# CPU.net
KiCad netlist of a schematic drawn in Altium Designer
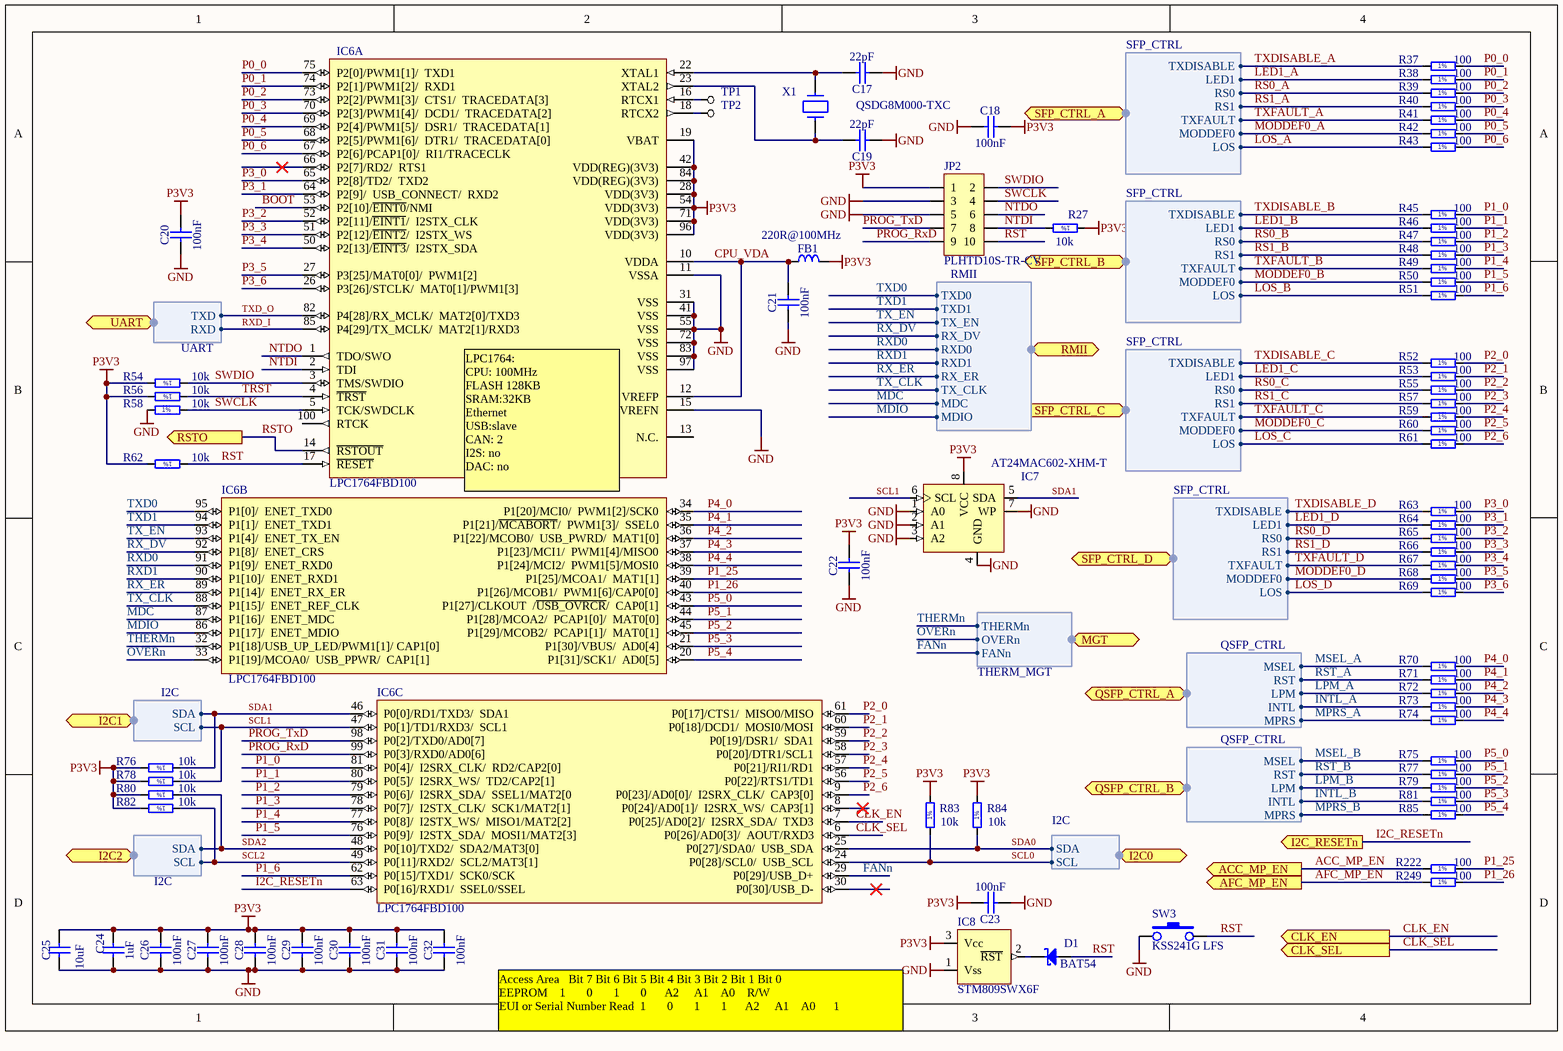
[diagram p0: CPU.SchDoc]

(export (version "E")
  (design (tool "Eeschema 10.0.6"))
  (components
    (comp (ref "C17")
      (value "22pF")
      (footprint "CAPC1005X55N")
      (description "Non-polarised capacitor")
      (fields
        (field (name "PART NUMBER") "CC0402_22PF_50V_5%_NP0")
        (field (name "VOLTAGE") "50V")
        (field (name "AUTHOR") "CERN DEM JLC")
      )
      (libsource (lib "Capacitors") (part "Capacitor - non polarized"))
    )
    (comp (ref "C18")
      (value "100nF")
      (footprint "CAPC0603X33N")
      (description "Non-polarised capacitor")
      (fields
        (field (name "PART NUMBER") "CC0201_100NF_6.3V_10%_X5R")
        (field (name "VOLTAGE") "6.3V")
        (field (name "AUTHOR") "CERN DEM JLC")
      )
      (libsource (lib "Capacitors") (part "Capacitor - non polarized"))
    )
    (comp (ref "C19")
      (value "22pF")
      (footprint "CAPC1005X55N")
      (description "Non-polarised capacitor")
      (fields
        (field (name "PART NUMBER") "CC0402_22PF_50V_5%_NP0")
        (field (name "VOLTAGE") "50V")
        (field (name "AUTHOR") "CERN DEM JLC")
      )
      (libsource (lib "Capacitors") (part "Capacitor - non polarized"))
    )
    (comp (ref "C20")
      (value "100nF")
      (footprint "CAPC0603X33N")
      (description "Non-polarised capacitor")
      (fields
        (field (name "PART NUMBER") "CC0201_100NF_6.3V_10%_X5R")
        (field (name "VOLTAGE") "6.3V")
        (field (name "AUTHOR") "CERN DEM JLC")
      )
      (libsource (lib "Capacitors") (part "Capacitor - non polarized"))
    )
    (comp (ref "C21")
      (value "100nF")
      (footprint "CAPC0603X33N")
      (description "Non-polarised capacitor")
      (fields
        (field (name "PART NUMBER") "CC0201_100NF_6.3V_10%_X5R")
        (field (name "VOLTAGE") "6.3V")
        (field (name "AUTHOR") "CERN DEM JLC")
      )
      (libsource (lib "Capacitors") (part "Capacitor - non polarized"))
    )
    (comp (ref "C22")
      (value "100nF")
      (footprint "CAPC0603X33N")
      (description "Non-polarised capacitor")
      (fields
        (field (name "PART NUMBER") "CC0201_100NF_6.3V_10%_X5R")
        (field (name "VOLTAGE") "6.3V")
        (field (name "AUTHOR") "CERN DEM JLC")
      )
      (libsource (lib "Capacitors") (part "Capacitor - non polarized"))
    )
    (comp (ref "C23")
      (value "100nF")
      (footprint "CAPC0603X33N")
      (description "Non-polarised capacitor")
      (fields
        (field (name "PART NUMBER") "CC0201_100NF_6.3V_10%_X5R")
        (field (name "VOLTAGE") "6.3V")
        (field (name "AUTHOR") "CERN DEM JLC")
      )
      (libsource (lib "Capacitors") (part "Capacitor - non polarized"))
    )
    (comp (ref "C24")
      (value "1uF")
      (footprint "CAPC1608X87N")
      (description "Non-polarised capacitor")
      (fields
        (field (name "PART NUMBER") "CC0603_1UF_25V_10%_X7R")
        (field (name "VOLTAGE") "25V")
        (field (name "AUTHOR") "CERN DEM JLC")
      )
      (libsource (lib "Capacitors") (part "Capacitor - non polarized"))
    )
    (comp (ref "C25")
      (value "10uF")
      (footprint "CAPC2012X135N")
      (description "Non-polarised capacitor")
      (fields
        (field (name "PART NUMBER") "CC0805_10UF_10V_10%_X7R")
        (field (name "VOLTAGE") "10V")
        (field (name "AUTHOR") "CERN DEM JLC")
      )
      (libsource (lib "Capacitors") (part "Capacitor - non polarized"))
    )
    (comp (ref "C26")
      (value "100nF")
      (footprint "CAPC0603X33N")
      (description "Non-polarised capacitor")
      (fields
        (field (name "PART NUMBER") "CC0201_100NF_6.3V_10%_X5R")
        (field (name "VOLTAGE") "6.3V")
        (field (name "AUTHOR") "CERN DEM JLC")
      )
      (libsource (lib "Capacitors") (part "Capacitor - non polarized"))
    )
    (comp (ref "C27")
      (value "100nF")
      (footprint "CAPC0603X33N")
      (description "Non-polarised capacitor")
      (fields
        (field (name "PART NUMBER") "CC0201_100NF_6.3V_10%_X5R")
        (field (name "VOLTAGE") "6.3V")
        (field (name "AUTHOR") "CERN DEM JLC")
      )
      (libsource (lib "Capacitors") (part "Capacitor - non polarized"))
    )
    (comp (ref "C28")
      (value "100nF")
      (footprint "CAPC0603X33N")
      (description "Non-polarised capacitor")
      (fields
        (field (name "PART NUMBER") "CC0201_100NF_6.3V_10%_X5R")
        (field (name "VOLTAGE") "6.3V")
        (field (name "AUTHOR") "CERN DEM JLC")
      )
      (libsource (lib "Capacitors") (part "Capacitor - non polarized"))
    )
    (comp (ref "C29")
      (value "100nF")
      (footprint "CAPC0603X33N")
      (description "Non-polarised capacitor")
      (fields
        (field (name "PART NUMBER") "CC0201_100NF_6.3V_10%_X5R")
        (field (name "VOLTAGE") "6.3V")
        (field (name "AUTHOR") "CERN DEM JLC")
      )
      (libsource (lib "Capacitors") (part "Capacitor - non polarized"))
    )
    (comp (ref "C30")
      (value "100nF")
      (footprint "CAPC0603X33N")
      (description "Non-polarised capacitor")
      (fields
        (field (name "PART NUMBER") "CC0201_100NF_6.3V_10%_X5R")
        (field (name "VOLTAGE") "6.3V")
        (field (name "AUTHOR") "CERN DEM JLC")
      )
      (libsource (lib "Capacitors") (part "Capacitor - non polarized"))
    )
    (comp (ref "C31")
      (value "100nF")
      (footprint "CAPC0603X33N")
      (description "Non-polarised capacitor")
      (fields
        (field (name "PART NUMBER") "CC0201_100NF_6.3V_10%_X5R")
        (field (name "VOLTAGE") "6.3V")
        (field (name "AUTHOR") "CERN DEM JLC")
      )
      (libsource (lib "Capacitors") (part "Capacitor - non polarized"))
    )
    (comp (ref "C32")
      (value "100nF")
      (footprint "CAPC0603X33N")
      (description "Non-polarised capacitor")
      (fields
        (field (name "PART NUMBER") "CC0201_100NF_6.3V_10%_X5R")
        (field (name "VOLTAGE") "6.3V")
        (field (name "AUTHOR") "CERN DEM JLC")
      )
      (libsource (lib "Capacitors") (part "Capacitor - non polarized"))
    )
    (comp (ref "D1")
      (value "BAT54")
      (footprint "SOT95P240X130-3N")
      (description "Diode Schottky  Anode Pin 1 Cathode Pin 3 (Pas de pin 2)")
      (fields
        (field (name "VOLTAGE") "30V")
        (field (name "POWER") "200mA")
        (field (name "AUTHOR") "CERN DEM JLC")
      )
      (libsource (lib "ICs And Semiconductors") (part "Diode Schottky A1C3"))
    )
    (comp (ref "FB1")
      (value "220R@100MHz")
      (footprint "INDC2012X105N")
      (description "Inductor")
      (fields
        (field (name "PART NUMBER") "IND0805_MURATA_BLM21PG221SN1D")
        (field (name "POWER") "2A")
        (field (name "AUTHOR") "CERN DEM JLC")
      )
      (libsource (lib "Inductors & Transformers") (part "Inductor"))
    )
    (comp (ref "IC6")
      (value "LPC1764FBD100")
      (footprint "LQFP100-LPC")
      (description "ARM Cortex-M3 procesor")
      (libsource (lib "LIBRARY_SCH") (part "UPC_LPC1764"))
    )
    (comp (ref "IC7")
      (value "AT24MAC602-XHM-T")
      (footprint "TSSOP-8")
      (description "Serial 2K EEPROM+ 48bit MAC")
      (libsource (lib "LIBRARY_SCH") (part "MEM_24MAC602"))
    )
    (comp (ref "IC8")
      (value "STM809SWX6F")
      (footprint "SOT-23")
      (description "2.93V  Reset circuit")
      (libsource (lib "LIBRARY_SCH") (part "VMON_STM809"))
    )
    (comp (ref "JP2")
      (value "PLHTD10S-TR-CV")
      (footprint "PLHTD10S-TR-CV")
      (description "1.27 mm dual row goldpin (Maritex)")
      (libsource (lib "LIBRARY_SCH") (part "CON_2x5 1.27 SMT Male"))
    )
    (comp (ref "R27")
      (value "10k")
      (footprint "RESC1005X40N")
      (description "Resistor - 1%")
      (fields
        (field (name "PART NUMBER") "R0402_10K_1%_0.0625W_100PPM")
        (field (name "POWER") "0.0625W")
        (field (name "AUTHOR") "CERN DEM JLC")
      )
      (libsource (lib "Resistors") (part "Resistor - 1%"))
    )
    (comp (ref "R37")
      (value "100")
      (footprint "RESC1005X40N")
      (description "Resistor - 1%")
      (fields
        (field (name "PART NUMBER") "R0402_100R_1%_0.0625W_100PPM")
        (field (name "POWER") "0.0625W")
        (field (name "AUTHOR") "CERN DEM JLC")
      )
      (libsource (lib "Resistors") (part "Resistor - 1%"))
    )
    (comp (ref "R38")
      (value "100")
      (footprint "RESC1005X40N")
      (description "Resistor - 1%")
      (fields
        (field (name "PART NUMBER") "R0402_100R_1%_0.0625W_100PPM")
        (field (name "POWER") "0.0625W")
        (field (name "AUTHOR") "CERN DEM JLC")
      )
      (libsource (lib "Resistors") (part "Resistor - 1%"))
    )
    (comp (ref "R39")
      (value "100")
      (footprint "RESC1005X40N")
      (description "Resistor - 1%")
      (fields
        (field (name "PART NUMBER") "R0402_100R_1%_0.0625W_100PPM")
        (field (name "POWER") "0.0625W")
        (field (name "AUTHOR") "CERN DEM JLC")
      )
      (libsource (lib "Resistors") (part "Resistor - 1%"))
    )
    (comp (ref "R40")
      (value "100")
      (footprint "RESC1005X40N")
      (description "Resistor - 1%")
      (fields
        (field (name "PART NUMBER") "R0402_100R_1%_0.0625W_100PPM")
        (field (name "POWER") "0.0625W")
        (field (name "AUTHOR") "CERN DEM JLC")
      )
      (libsource (lib "Resistors") (part "Resistor - 1%"))
    )
    (comp (ref "R41")
      (value "100")
      (footprint "RESC1005X40N")
      (description "Resistor - 1%")
      (fields
        (field (name "PART NUMBER") "R0402_100R_1%_0.0625W_100PPM")
        (field (name "POWER") "0.0625W")
        (field (name "AUTHOR") "CERN DEM JLC")
      )
      (libsource (lib "Resistors") (part "Resistor - 1%"))
    )
    (comp (ref "R42")
      (value "100")
      (footprint "RESC1005X40N")
      (description "Resistor - 1%")
      (fields
        (field (name "PART NUMBER") "R0402_100R_1%_0.0625W_100PPM")
        (field (name "POWER") "0.0625W")
        (field (name "AUTHOR") "CERN DEM JLC")
      )
      (libsource (lib "Resistors") (part "Resistor - 1%"))
    )
    (comp (ref "R43")
      (value "100")
      (footprint "RESC1005X40N")
      (description "Resistor - 1%")
      (fields
        (field (name "PART NUMBER") "R0402_100R_1%_0.0625W_100PPM")
        (field (name "POWER") "0.0625W")
        (field (name "AUTHOR") "CERN DEM JLC")
      )
      (libsource (lib "Resistors") (part "Resistor - 1%"))
    )
    (comp (ref "R45")
      (value "100")
      (footprint "RESC1005X40N")
      (description "Resistor - 1%")
      (fields
        (field (name "PART NUMBER") "R0402_100R_1%_0.0625W_100PPM")
        (field (name "POWER") "0.0625W")
        (field (name "AUTHOR") "CERN DEM JLC")
      )
      (libsource (lib "Resistors") (part "Resistor - 1%"))
    )
    (comp (ref "R46")
      (value "100")
      (footprint "RESC1005X40N")
      (description "Resistor - 1%")
      (fields
        (field (name "PART NUMBER") "R0402_100R_1%_0.0625W_100PPM")
        (field (name "POWER") "0.0625W")
        (field (name "AUTHOR") "CERN DEM JLC")
      )
      (libsource (lib "Resistors") (part "Resistor - 1%"))
    )
    (comp (ref "R47")
      (value "100")
      (footprint "RESC1005X40N")
      (description "Resistor - 1%")
      (fields
        (field (name "PART NUMBER") "R0402_100R_1%_0.0625W_100PPM")
        (field (name "POWER") "0.0625W")
        (field (name "AUTHOR") "CERN DEM JLC")
      )
      (libsource (lib "Resistors") (part "Resistor - 1%"))
    )
    (comp (ref "R48")
      (value "100")
      (footprint "RESC1005X40N")
      (description "Resistor - 1%")
      (fields
        (field (name "PART NUMBER") "R0402_100R_1%_0.0625W_100PPM")
        (field (name "POWER") "0.0625W")
        (field (name "AUTHOR") "CERN DEM JLC")
      )
      (libsource (lib "Resistors") (part "Resistor - 1%"))
    )
    (comp (ref "R49")
      (value "100")
      (footprint "RESC1005X40N")
      (description "Resistor - 1%")
      (fields
        (field (name "PART NUMBER") "R0402_100R_1%_0.0625W_100PPM")
        (field (name "POWER") "0.0625W")
        (field (name "AUTHOR") "CERN DEM JLC")
      )
      (libsource (lib "Resistors") (part "Resistor - 1%"))
    )
    (comp (ref "R50")
      (value "100")
      (footprint "RESC1005X40N")
      (description "Resistor - 1%")
      (fields
        (field (name "PART NUMBER") "R0402_100R_1%_0.0625W_100PPM")
        (field (name "POWER") "0.0625W")
        (field (name "AUTHOR") "CERN DEM JLC")
      )
      (libsource (lib "Resistors") (part "Resistor - 1%"))
    )
    (comp (ref "R51")
      (value "100")
      (footprint "RESC1005X40N")
      (description "Resistor - 1%")
      (fields
        (field (name "PART NUMBER") "R0402_100R_1%_0.0625W_100PPM")
        (field (name "POWER") "0.0625W")
        (field (name "AUTHOR") "CERN DEM JLC")
      )
      (libsource (lib "Resistors") (part "Resistor - 1%"))
    )
    (comp (ref "R52")
      (value "100")
      (footprint "RESC1005X40N")
      (description "Resistor - 1%")
      (fields
        (field (name "PART NUMBER") "R0402_100R_1%_0.0625W_100PPM")
        (field (name "POWER") "0.0625W")
        (field (name "AUTHOR") "CERN DEM JLC")
      )
      (libsource (lib "Resistors") (part "Resistor - 1%"))
    )
    (comp (ref "R53")
      (value "100")
      (footprint "RESC1005X40N")
      (description "Resistor - 1%")
      (fields
        (field (name "PART NUMBER") "R0402_100R_1%_0.0625W_100PPM")
        (field (name "POWER") "0.0625W")
        (field (name "AUTHOR") "CERN DEM JLC")
      )
      (libsource (lib "Resistors") (part "Resistor - 1%"))
    )
    (comp (ref "R54")
      (value "10k")
      (footprint "RESC1005X40N")
      (description "Resistor - 1%")
      (fields
        (field (name "PART NUMBER") "R0402_10K_1%_0.0625W_100PPM")
        (field (name "POWER") "0.0625W")
        (field (name "AUTHOR") "CERN DEM JLC")
      )
      (libsource (lib "Resistors") (part "Resistor - 1%"))
    )
    (comp (ref "R55")
      (value "100")
      (footprint "RESC1005X40N")
      (description "Resistor - 1%")
      (fields
        (field (name "PART NUMBER") "R0402_100R_1%_0.0625W_100PPM")
        (field (name "POWER") "0.0625W")
        (field (name "AUTHOR") "CERN DEM JLC")
      )
      (libsource (lib "Resistors") (part "Resistor - 1%"))
    )
    (comp (ref "R56")
      (value "10k")
      (footprint "RESC1005X40N")
      (description "Resistor - 1%")
      (fields
        (field (name "PART NUMBER") "R0402_10K_1%_0.0625W_100PPM")
        (field (name "POWER") "0.0625W")
        (field (name "AUTHOR") "CERN DEM JLC")
      )
      (libsource (lib "Resistors") (part "Resistor - 1%"))
    )
    (comp (ref "R57")
      (value "100")
      (footprint "RESC1005X40N")
      (description "Resistor - 1%")
      (fields
        (field (name "PART NUMBER") "R0402_100R_1%_0.0625W_100PPM")
        (field (name "POWER") "0.0625W")
        (field (name "AUTHOR") "CERN DEM JLC")
      )
      (libsource (lib "Resistors") (part "Resistor - 1%"))
    )
    (comp (ref "R58")
      (value "10k")
      (footprint "RESC1005X40N")
      (description "Resistor - 1%")
      (fields
        (field (name "PART NUMBER") "R0402_10K_1%_0.0625W_100PPM")
        (field (name "POWER") "0.0625W")
        (field (name "AUTHOR") "CERN DEM JLC")
      )
      (libsource (lib "Resistors") (part "Resistor - 1%"))
    )
    (comp (ref "R59")
      (value "100")
      (footprint "RESC1005X40N")
      (description "Resistor - 1%")
      (fields
        (field (name "PART NUMBER") "R0402_100R_1%_0.0625W_100PPM")
        (field (name "POWER") "0.0625W")
        (field (name "AUTHOR") "CERN DEM JLC")
      )
      (libsource (lib "Resistors") (part "Resistor - 1%"))
    )
    (comp (ref "R60")
      (value "100")
      (footprint "RESC1005X40N")
      (description "Resistor - 1%")
      (fields
        (field (name "PART NUMBER") "R0402_100R_1%_0.0625W_100PPM")
        (field (name "POWER") "0.0625W")
        (field (name "AUTHOR") "CERN DEM JLC")
      )
      (libsource (lib "Resistors") (part "Resistor - 1%"))
    )
    (comp (ref "R61")
      (value "100")
      (footprint "RESC1005X40N")
      (description "Resistor - 1%")
      (fields
        (field (name "PART NUMBER") "R0402_100R_1%_0.0625W_100PPM")
        (field (name "POWER") "0.0625W")
        (field (name "AUTHOR") "CERN DEM JLC")
      )
      (libsource (lib "Resistors") (part "Resistor - 1%"))
    )
    (comp (ref "R62")
      (value "10k")
      (footprint "RESC1005X40N")
      (description "Resistor - 1%")
      (fields
        (field (name "PART NUMBER") "R0402_10K_1%_0.0625W_100PPM")
        (field (name "POWER") "0.0625W")
        (field (name "AUTHOR") "CERN DEM JLC")
      )
      (libsource (lib "Resistors") (part "Resistor - 1%"))
    )
    (comp (ref "R63")
      (value "100")
      (footprint "RESC1005X40N")
      (description "Resistor - 1%")
      (fields
        (field (name "PART NUMBER") "R0402_100R_1%_0.0625W_100PPM")
        (field (name "POWER") "0.0625W")
        (field (name "AUTHOR") "CERN DEM JLC")
      )
      (libsource (lib "Resistors") (part "Resistor - 1%"))
    )
    (comp (ref "R64")
      (value "100")
      (footprint "RESC1005X40N")
      (description "Resistor - 1%")
      (fields
        (field (name "PART NUMBER") "R0402_100R_1%_0.0625W_100PPM")
        (field (name "POWER") "0.0625W")
        (field (name "AUTHOR") "CERN DEM JLC")
      )
      (libsource (lib "Resistors") (part "Resistor - 1%"))
    )
    (comp (ref "R65")
      (value "100")
      (footprint "RESC1005X40N")
      (description "Resistor - 1%")
      (fields
        (field (name "PART NUMBER") "R0402_100R_1%_0.0625W_100PPM")
        (field (name "POWER") "0.0625W")
        (field (name "AUTHOR") "CERN DEM JLC")
      )
      (libsource (lib "Resistors") (part "Resistor - 1%"))
    )
    (comp (ref "R66")
      (value "100")
      (footprint "RESC1005X40N")
      (description "Resistor - 1%")
      (fields
        (field (name "PART NUMBER") "R0402_100R_1%_0.0625W_100PPM")
        (field (name "POWER") "0.0625W")
        (field (name "AUTHOR") "CERN DEM JLC")
      )
      (libsource (lib "Resistors") (part "Resistor - 1%"))
    )
    (comp (ref "R67")
      (value "100")
      (footprint "RESC1005X40N")
      (description "Resistor - 1%")
      (fields
        (field (name "PART NUMBER") "R0402_100R_1%_0.0625W_100PPM")
        (field (name "POWER") "0.0625W")
        (field (name "AUTHOR") "CERN DEM JLC")
      )
      (libsource (lib "Resistors") (part "Resistor - 1%"))
    )
    (comp (ref "R68")
      (value "100")
      (footprint "RESC1005X40N")
      (description "Resistor - 1%")
      (fields
        (field (name "PART NUMBER") "R0402_100R_1%_0.0625W_100PPM")
        (field (name "POWER") "0.0625W")
        (field (name "AUTHOR") "CERN DEM JLC")
      )
      (libsource (lib "Resistors") (part "Resistor - 1%"))
    )
    (comp (ref "R69")
      (value "100")
      (footprint "RESC1005X40N")
      (description "Resistor - 1%")
      (fields
        (field (name "PART NUMBER") "R0402_100R_1%_0.0625W_100PPM")
        (field (name "POWER") "0.0625W")
        (field (name "AUTHOR") "CERN DEM JLC")
      )
      (libsource (lib "Resistors") (part "Resistor - 1%"))
    )
    (comp (ref "R70")
      (value "100")
      (footprint "RESC1005X40N")
      (description "Resistor - 1%")
      (fields
        (field (name "PART NUMBER") "R0402_100R_1%_0.0625W_100PPM")
        (field (name "POWER") "0.0625W")
        (field (name "AUTHOR") "CERN DEM JLC")
      )
      (libsource (lib "Resistors") (part "Resistor - 1%"))
    )
    (comp (ref "R71")
      (value "100")
      (footprint "RESC1005X40N")
      (description "Resistor - 1%")
      (fields
        (field (name "PART NUMBER") "R0402_100R_1%_0.0625W_100PPM")
        (field (name "POWER") "0.0625W")
        (field (name "AUTHOR") "CERN DEM JLC")
      )
      (libsource (lib "Resistors") (part "Resistor - 1%"))
    )
    (comp (ref "R72")
      (value "100")
      (footprint "RESC1005X40N")
      (description "Resistor - 1%")
      (fields
        (field (name "PART NUMBER") "R0402_100R_1%_0.0625W_100PPM")
        (field (name "POWER") "0.0625W")
        (field (name "AUTHOR") "CERN DEM JLC")
      )
      (libsource (lib "Resistors") (part "Resistor - 1%"))
    )
    (comp (ref "R73")
      (value "100")
      (footprint "RESC1005X40N")
      (description "Resistor - 1%")
      (fields
        (field (name "PART NUMBER") "R0402_100R_1%_0.0625W_100PPM")
        (field (name "POWER") "0.0625W")
        (field (name "AUTHOR") "CERN DEM JLC")
      )
      (libsource (lib "Resistors") (part "Resistor - 1%"))
    )
    (comp (ref "R74")
      (value "100")
      (footprint "RESC1005X40N")
      (description "Resistor - 1%")
      (fields
        (field (name "PART NUMBER") "R0402_100R_1%_0.0625W_100PPM")
        (field (name "POWER") "0.0625W")
        (field (name "AUTHOR") "CERN DEM JLC")
      )
      (libsource (lib "Resistors") (part "Resistor - 1%"))
    )
    (comp (ref "R75")
      (value "100")
      (footprint "RESC1005X40N")
      (description "Resistor - 1%")
      (fields
        (field (name "PART NUMBER") "R0402_100R_1%_0.0625W_100PPM")
        (field (name "POWER") "0.0625W")
        (field (name "AUTHOR") "CERN DEM JLC")
      )
      (libsource (lib "Resistors") (part "Resistor - 1%"))
    )
    (comp (ref "R76")
      (value "10k")
      (footprint "RESC1005X40N")
      (description "Resistor - 1%")
      (fields
        (field (name "PART NUMBER") "R0402_10K_1%_0.0625W_100PPM")
        (field (name "POWER") "0.0625W")
        (field (name "AUTHOR") "CERN DEM JLC")
      )
      (libsource (lib "Resistors") (part "Resistor - 1%"))
    )
    (comp (ref "R77")
      (value "100")
      (footprint "RESC1005X40N")
      (description "Resistor - 1%")
      (fields
        (field (name "PART NUMBER") "R0402_100R_1%_0.0625W_100PPM")
        (field (name "POWER") "0.0625W")
        (field (name "AUTHOR") "CERN DEM JLC")
      )
      (libsource (lib "Resistors") (part "Resistor - 1%"))
    )
    (comp (ref "R78")
      (value "10k")
      (footprint "RESC1005X40N")
      (description "Resistor - 1%")
      (fields
        (field (name "PART NUMBER") "R0402_10K_1%_0.0625W_100PPM")
        (field (name "POWER") "0.0625W")
        (field (name "AUTHOR") "CERN DEM JLC")
      )
      (libsource (lib "Resistors") (part "Resistor - 1%"))
    )
    (comp (ref "R79")
      (value "100")
      (footprint "RESC1005X40N")
      (description "Resistor - 1%")
      (fields
        (field (name "PART NUMBER") "R0402_100R_1%_0.0625W_100PPM")
        (field (name "POWER") "0.0625W")
        (field (name "AUTHOR") "CERN DEM JLC")
      )
      (libsource (lib "Resistors") (part "Resistor - 1%"))
    )
    (comp (ref "R80")
      (value "10k")
      (footprint "RESC1005X40N")
      (description "Resistor - 1%")
      (fields
        (field (name "PART NUMBER") "R0402_10K_1%_0.0625W_100PPM")
        (field (name "POWER") "0.0625W")
        (field (name "AUTHOR") "CERN DEM JLC")
      )
      (libsource (lib "Resistors") (part "Resistor - 1%"))
    )
    (comp (ref "R81")
      (value "100")
      (footprint "RESC1005X40N")
      (description "Resistor - 1%")
      (fields
        (field (name "PART NUMBER") "R0402_100R_1%_0.0625W_100PPM")
        (field (name "POWER") "0.0625W")
        (field (name "AUTHOR") "CERN DEM JLC")
      )
      (libsource (lib "Resistors") (part "Resistor - 1%"))
    )
    (comp (ref "R82")
      (value "10k")
      (footprint "RESC1005X40N")
      (description "Resistor - 1%")
      (fields
        (field (name "PART NUMBER") "R0402_10K_1%_0.0625W_100PPM")
        (field (name "POWER") "0.0625W")
        (field (name "AUTHOR") "CERN DEM JLC")
      )
      (libsource (lib "Resistors") (part "Resistor - 1%"))
    )
    (comp (ref "R83")
      (value "10k")
      (footprint "RESC1005X40N")
      (description "Resistor - 1%")
      (fields
        (field (name "PART NUMBER") "R0402_10K_1%_0.0625W_100PPM")
        (field (name "POWER") "0.0625W")
        (field (name "AUTHOR") "CERN DEM JLC")
      )
      (libsource (lib "Resistors") (part "Resistor - 1%"))
    )
    (comp (ref "R84")
      (value "10k")
      (footprint "RESC1005X40N")
      (description "Resistor - 1%")
      (fields
        (field (name "PART NUMBER") "R0402_10K_1%_0.0625W_100PPM")
        (field (name "POWER") "0.0625W")
        (field (name "AUTHOR") "CERN DEM JLC")
      )
      (libsource (lib "Resistors") (part "Resistor - 1%"))
    )
    (comp (ref "R85")
      (value "100")
      (footprint "RESC1005X40N")
      (description "Resistor - 1%")
      (fields
        (field (name "PART NUMBER") "R0402_100R_1%_0.0625W_100PPM")
        (field (name "POWER") "0.0625W")
        (field (name "AUTHOR") "CERN DEM JLC")
      )
      (libsource (lib "Resistors") (part "Resistor - 1%"))
    )
    (comp (ref "R222")
      (value "100")
      (footprint "RESC1005X40N")
      (description "Resistor - 1%")
      (fields
        (field (name "PART NUMBER") "R0402_100R_1%_0.0625W_100PPM")
        (field (name "POWER") "0.0625W")
        (field (name "AUTHOR") "CERN DEM JLC")
      )
      (libsource (lib "Resistors") (part "Resistor - 1%"))
    )
    (comp (ref "R249")
      (value "100")
      (footprint "RESC1005X40N")
      (description "Resistor - 1%")
      (fields
        (field (name "PART NUMBER") "R0402_100R_1%_0.0625W_100PPM")
        (field (name "POWER") "0.0625W")
        (field (name "AUTHOR") "CERN DEM JLC")
      )
      (libsource (lib "Resistors") (part "Resistor - 1%"))
    )
    (comp (ref "SW3")
      (value "KSS241G LFS")
      (footprint "KSS241G LFS")
      (description "Push button")
      (libsource (lib "LIBRARY_SCH") (part "SW-TACT_SMD_RA_mini"))
    )
    (comp (ref "TP1")
      (value "TP")
      (footprint "TP")
      (description "Testpoint")
      (libsource (lib "LIBRARY_SCH") (part "TP"))
    )
    (comp (ref "TP2")
      (value "TP")
      (footprint "TP")
      (description "Testpoint")
      (libsource (lib "LIBRARY_SCH") (part "TP"))
    )
    (comp (ref "X1")
      (value "QSDG8M000-TXC")
      (footprint "XTAL_5.0*3.2")
      (description "miniature crystal oscillator (Maritex) QSDG8M000-TXC")
      (libsource (lib "LIBRARY_SCH") (part "X_CRYSTAL_SMD_5.0*3.2"))
    )
  )
  (nets
    (net (code "7") (name "/ACC_MP_EN") (class "Default")
      (node (ref "R222") (pin "1") (pinfunction "1_1") (pintype "passive"))
    )
    (net (code "8") (name "/AFC_MP_EN") (class "Default")
      (node (ref "R249") (pin "1") (pinfunction "1_1") (pintype "passive"))
    )
    (net (code "9") (name "/BOOT") (class "Default")
      (node (ref "IC6") (pin "53") (pinfunction "P2[10]/~{EINT0}/NMI_53") (pintype "bidirectional"))
    )
    (net (code "10") (name "/CLK_EN") (class "Default")
      (node (ref "IC6") (pin "7") (pinfunction "P0[25]/AD0[2]/__I2SRX_SDA/__TXD3_7") (pintype "bidirectional"))
    )
    (net (code "11") (name "/CLK_SEL") (class "Default")
      (node (ref "IC6") (pin "6") (pinfunction "P0[26]/AD0[3]/__AOUT/RXD3_6") (pintype "bidirectional"))
    )
    (net (code "12") (name "/CPU_VDA") (class "Default")
      (node (ref "C21") (pin "2") (pinfunction "2_2") (pintype "passive"))
      (node (ref "FB1") (pin "1") (pinfunction "1_1") (pintype "passive"))
      (node (ref "IC6") (pin "10") (pinfunction "VDDA_10") (pintype "power_in"))
      (node (ref "IC6") (pin "12") (pinfunction "VREFP_12") (pintype "power_in"))
    )
    (net (code "13") (name "/FANn") (class "Default")
      (node (ref "IC6") (pin "29") (pinfunction "P0[29]/USB_D+_29") (pintype "bidirectional"))
    )
    (net (code "14") (name "/I2C_RESETn") (class "Default")
      (node (ref "IC6") (pin "63") (pinfunction "P0[16]/RXD1/__SSEL0/SSEL_63") (pintype "bidirectional"))
    )
    (net (code "15") (name "/INTL_A") (class "Default")
      (node (ref "R73") (pin "1") (pinfunction "1_1") (pintype "passive"))
    )
    (net (code "16") (name "/INTL_B") (class "Default")
      (node (ref "R81") (pin "1") (pinfunction "1_1") (pintype "passive"))
    )
    (net (code "17") (name "/LED1_A") (class "Default")
      (node (ref "R38") (pin "1") (pinfunction "1_1") (pintype "passive"))
    )
    (net (code "18") (name "/LED1_B") (class "Default")
      (node (ref "R46") (pin "1") (pinfunction "1_1") (pintype "passive"))
    )
    (net (code "19") (name "/LED1_C") (class "Default")
      (node (ref "R53") (pin "1") (pinfunction "1_1") (pintype "passive"))
    )
    (net (code "20") (name "/LED1_D") (class "Default")
      (node (ref "R64") (pin "1") (pinfunction "1_1") (pintype "passive"))
    )
    (net (code "21") (name "/LOS_A") (class "Default")
      (node (ref "R43") (pin "1") (pinfunction "1_1") (pintype "passive"))
    )
    (net (code "22") (name "/LOS_B") (class "Default")
      (node (ref "R51") (pin "1") (pinfunction "1_1") (pintype "passive"))
    )
    (net (code "23") (name "/LOS_C") (class "Default")
      (node (ref "R61") (pin "1") (pinfunction "1_1") (pintype "passive"))
    )
    (net (code "24") (name "/LOS_D") (class "Default")
      (node (ref "R69") (pin "1") (pinfunction "1_1") (pintype "passive"))
    )
    (net (code "25") (name "/LPM_A") (class "Default")
      (node (ref "R72") (pin "1") (pinfunction "1_1") (pintype "passive"))
    )
    (net (code "26") (name "/LPM_B") (class "Default")
      (node (ref "R79") (pin "1") (pinfunction "1_1") (pintype "passive"))
    )
    (net (code "27") (name "/MDC") (class "Default")
      (node (ref "IC6") (pin "87") (pinfunction "P1[16]/__ENET_MDC_87") (pintype "bidirectional"))
    )
    (net (code "28") (name "/MDIO") (class "Default")
      (node (ref "IC6") (pin "86") (pinfunction "P1[17]/__ENET_MDIO_86") (pintype "bidirectional"))
    )
    (net (code "29") (name "/MODDEF0_A") (class "Default")
      (node (ref "R42") (pin "1") (pinfunction "1_1") (pintype "passive"))
    )
    (net (code "30") (name "/MODDEF0_B") (class "Default")
      (node (ref "R50") (pin "1") (pinfunction "1_1") (pintype "passive"))
    )
    (net (code "31") (name "/MODDEF0_C") (class "Default")
      (node (ref "R60") (pin "1") (pinfunction "1_1") (pintype "passive"))
    )
    (net (code "32") (name "/MODDEF0_D") (class "Default")
      (node (ref "R68") (pin "1") (pinfunction "1_1") (pintype "passive"))
    )
    (net (code "33") (name "/MPRS_A") (class "Default")
      (node (ref "R74") (pin "1") (pinfunction "1_1") (pintype "passive"))
    )
    (net (code "34") (name "/MPRS_B") (class "Default")
      (node (ref "R85") (pin "1") (pinfunction "1_1") (pintype "passive"))
    )
    (net (code "35") (name "/MSEL_A") (class "Default")
      (node (ref "R70") (pin "1") (pinfunction "1_1") (pintype "passive"))
    )
    (net (code "36") (name "/MSEL_B") (class "Default")
      (node (ref "R75") (pin "1") (pinfunction "1_1") (pintype "passive"))
    )
    (net (code "37") (name "/NTDI") (class "Default")
      (node (ref "IC6") (pin "2") (pinfunction "TDI_2") (pintype "input"))
      (node (ref "JP2") (pin "8") (pinfunction "8_8") (pintype "passive"))
      (node (ref "R27") (pin "2") (pinfunction "2_2") (pintype "passive"))
    )
    (net (code "38") (name "/NTDO") (class "Default")
      (node (ref "IC6") (pin "1") (pinfunction "TDO/SWO_1") (pintype "output"))
      (node (ref "JP2") (pin "6") (pinfunction "6_6") (pintype "passive"))
    )
    (net (code "39") (name "/OVERn") (class "Default")
      (node (ref "IC6") (pin "33") (pinfunction "P1[19]/MCOA0/__USB_PPWR/__CAP1[1]_33") (pintype "bidirectional"))
    )
    (net (code "40") (name "/P0_0") (class "Default")
      (node (ref "IC6") (pin "75") (pinfunction "P2[0]/PWM1[1]/__TXD1_75") (pintype "bidirectional"))
      (node (ref "R37") (pin "2") (pinfunction "2_2") (pintype "passive"))
    )
    (net (code "41") (name "/P0_1") (class "Default")
      (node (ref "IC6") (pin "74") (pinfunction "P2[1]/PWM1[2]/__RXD1_74") (pintype "bidirectional"))
      (node (ref "R38") (pin "2") (pinfunction "2_2") (pintype "passive"))
    )
    (net (code "42") (name "/P0_2") (class "Default")
      (node (ref "IC6") (pin "73") (pinfunction "P2[2]/PWM1[3]/__CTS1/__TRACEDATA[3]_73") (pintype "bidirectional"))
      (node (ref "R39") (pin "2") (pinfunction "2_2") (pintype "passive"))
    )
    (net (code "43") (name "/P0_3") (class "Default")
      (node (ref "IC6") (pin "70") (pinfunction "P2[3]/PWM1[4]/__DCD1/__TRACEDATA[2]_70") (pintype "bidirectional"))
      (node (ref "R40") (pin "2") (pinfunction "2_2") (pintype "passive"))
    )
    (net (code "44") (name "/P0_4") (class "Default")
      (node (ref "IC6") (pin "69") (pinfunction "P2[4]/PWM1[5]/__DSR1/__TRACEDATA[1]_69") (pintype "bidirectional"))
      (node (ref "R41") (pin "2") (pinfunction "2_2") (pintype "passive"))
    )
    (net (code "45") (name "/P0_5") (class "Default")
      (node (ref "IC6") (pin "68") (pinfunction "P2[5]/PWM1[6]/__DTR1/__TRACEDATA[0]_68") (pintype "bidirectional"))
      (node (ref "R42") (pin "2") (pinfunction "2_2") (pintype "passive"))
    )
    (net (code "46") (name "/P0_6") (class "Default")
      (node (ref "IC6") (pin "67") (pinfunction "P2[6]/PCAP1[0]/__RI1/TRACECLK_67") (pintype "bidirectional"))
      (node (ref "R43") (pin "2") (pinfunction "2_2") (pintype "passive"))
    )
    (net (code "47") (name "/P1_0") (class "Default")
      (node (ref "IC6") (pin "81") (pinfunction "P0[4]/__I2SRX_CLK/__RD2/CAP2[0]_81") (pintype "bidirectional"))
      (node (ref "R45") (pin "2") (pinfunction "2_2") (pintype "passive"))
    )
    (net (code "48") (name "/P1_1") (class "Default")
      (node (ref "IC6") (pin "80") (pinfunction "P0[5]/__I2SRX_WS/__TD2/CAP2[1]_80") (pintype "bidirectional"))
      (node (ref "R46") (pin "2") (pinfunction "2_2") (pintype "passive"))
    )
    (net (code "49") (name "/P1_2") (class "Default")
      (node (ref "IC6") (pin "79") (pinfunction "P0[6]/__I2SRX_SDA/__SSEL1/MAT2[0_79") (pintype "bidirectional"))
      (node (ref "R47") (pin "2") (pinfunction "2_2") (pintype "passive"))
    )
    (net (code "50") (name "/P1_3") (class "Default")
      (node (ref "IC6") (pin "78") (pinfunction "P0[7]/__I2STX_CLK/__SCK1/MAT2[1]_78") (pintype "bidirectional"))
      (node (ref "R48") (pin "2") (pinfunction "2_2") (pintype "passive"))
    )
    (net (code "51") (name "/P1_4") (class "Default")
      (node (ref "IC6") (pin "77") (pinfunction "P0[8]/__I2STX_WS/__MISO1/MAT2[2]_77") (pintype "bidirectional"))
      (node (ref "R49") (pin "2") (pinfunction "2_2") (pintype "passive"))
    )
    (net (code "52") (name "/P1_5") (class "Default")
      (node (ref "IC6") (pin "76") (pinfunction "P0[9]/__I2STX_SDA/__MOSI1/MAT2[3]_76") (pintype "bidirectional"))
      (node (ref "R50") (pin "2") (pinfunction "2_2") (pintype "passive"))
    )
    (net (code "53") (name "/P1_6") (class "Default")
      (node (ref "IC6") (pin "62") (pinfunction "P0[15]/TXD1/__SCK0/SCK_62") (pintype "bidirectional"))
      (node (ref "R51") (pin "2") (pinfunction "2_2") (pintype "passive"))
    )
    (net (code "54") (name "/P1_25") (class "Default")
      (node (ref "IC6") (pin "39") (pinfunction "P1[25]/MCOA1/__MAT1[1]_39") (pintype "bidirectional"))
      (node (ref "R222") (pin "2") (pinfunction "2_2") (pintype "passive"))
    )
    (net (code "55") (name "/P1_26") (class "Default")
      (node (ref "IC6") (pin "40") (pinfunction "P1[26]/MCOB1/__PWM1[6]/CAP0[0]_40") (pintype "bidirectional"))
      (node (ref "R249") (pin "2") (pinfunction "2_2") (pintype "passive"))
    )
    (net (code "56") (name "/P2_0") (class "Default")
      (node (ref "IC6") (pin "61") (pinfunction "P0[17]/CTS1/__MISO0/MISO_61") (pintype "bidirectional"))
      (node (ref "R52") (pin "2") (pinfunction "2_2") (pintype "passive"))
    )
    (net (code "57") (name "/P2_1") (class "Default")
      (node (ref "IC6") (pin "60") (pinfunction "P0[18]/DCD1/__MOSI0/MOSI_60") (pintype "bidirectional"))
      (node (ref "R53") (pin "2") (pinfunction "2_2") (pintype "passive"))
    )
    (net (code "58") (name "/P2_2") (class "Default")
      (node (ref "IC6") (pin "59") (pinfunction "P0[19]/DSR1/__SDA1_59") (pintype "bidirectional"))
      (node (ref "R55") (pin "2") (pinfunction "2_2") (pintype "passive"))
    )
    (net (code "59") (name "/P2_3") (class "Default")
      (node (ref "IC6") (pin "58") (pinfunction "P0[20]/DTR1/SCL1_58") (pintype "bidirectional"))
      (node (ref "R57") (pin "2") (pinfunction "2_2") (pintype "passive"))
    )
    (net (code "60") (name "/P2_4") (class "Default")
      (node (ref "IC6") (pin "57") (pinfunction "P0[21]/RI1/RD1_57") (pintype "bidirectional"))
      (node (ref "R59") (pin "2") (pinfunction "2_2") (pintype "passive"))
    )
    (net (code "61") (name "/P2_5") (class "Default")
      (node (ref "IC6") (pin "56") (pinfunction "P0[22]/RTS1/TD1_56") (pintype "bidirectional"))
      (node (ref "R60") (pin "2") (pinfunction "2_2") (pintype "passive"))
    )
    (net (code "62") (name "/P2_6") (class "Default")
      (node (ref "IC6") (pin "9") (pinfunction "P0[23]/AD0[0]/__I2SRX_CLK/__CAP3[0]_9") (pintype "bidirectional"))
      (node (ref "R61") (pin "2") (pinfunction "2_2") (pintype "passive"))
    )
    (net (code "63") (name "/P3_0") (class "Default")
      (node (ref "IC6") (pin "65") (pinfunction "P2[8]/TD2/__TXD2_65") (pintype "bidirectional"))
      (node (ref "R63") (pin "2") (pinfunction "2_2") (pintype "passive"))
    )
    (net (code "64") (name "/P3_1") (class "Default")
      (node (ref "IC6") (pin "64") (pinfunction "P2[9]/__USB_CONNECT/__RXD2_64") (pintype "bidirectional"))
      (node (ref "R64") (pin "2") (pinfunction "2_2") (pintype "passive"))
    )
    (net (code "65") (name "/P3_2") (class "Default")
      (node (ref "IC6") (pin "52") (pinfunction "P2[11]/~{EINT1}/__I2STX_CLK_52") (pintype "bidirectional"))
      (node (ref "R65") (pin "2") (pinfunction "2_2") (pintype "passive"))
    )
    (net (code "66") (name "/P3_3") (class "Default")
      (node (ref "IC6") (pin "51") (pinfunction "P2[12]/~{EINT2}/__I2STX_WS_51") (pintype "bidirectional"))
      (node (ref "R66") (pin "2") (pinfunction "2_2") (pintype "passive"))
    )
    (net (code "67") (name "/P3_4") (class "Default")
      (node (ref "IC6") (pin "50") (pinfunction "P2[13]/~{EINT3}/__I2STX_SDA_50") (pintype "bidirectional"))
      (node (ref "R67") (pin "2") (pinfunction "2_2") (pintype "passive"))
    )
    (net (code "68") (name "/P3_5") (class "Default")
      (node (ref "IC6") (pin "27") (pinfunction "P3[25]/MAT0[0]/__PWM1[2]_27") (pintype "bidirectional"))
      (node (ref "R68") (pin "2") (pinfunction "2_2") (pintype "passive"))
    )
    (net (code "69") (name "/P3_6") (class "Default")
      (node (ref "IC6") (pin "26") (pinfunction "P3[26]/STCLK/__MAT0[1]/PWM1[3]_26") (pintype "bidirectional"))
      (node (ref "R69") (pin "2") (pinfunction "2_2") (pintype "passive"))
    )
    (net (code "70") (name "/P4_0") (class "Default")
      (node (ref "IC6") (pin "34") (pinfunction "P1[20]/MCI0/__PWM1[2]/SCK0_34") (pintype "bidirectional"))
      (node (ref "R70") (pin "2") (pinfunction "2_2") (pintype "passive"))
    )
    (net (code "71") (name "/P4_1") (class "Default")
      (node (ref "IC6") (pin "35") (pinfunction "P1[21]/~{MCABORT}/__PWM1[3]/__SSEL0_35") (pintype "bidirectional"))
      (node (ref "R71") (pin "2") (pinfunction "2_2") (pintype "passive"))
    )
    (net (code "72") (name "/P4_2") (class "Default")
      (node (ref "IC6") (pin "36") (pinfunction "P1[22]/MCOB0/__USB_PWRD/__MAT1[0]_36") (pintype "bidirectional"))
      (node (ref "R72") (pin "2") (pinfunction "2_2") (pintype "passive"))
    )
    (net (code "73") (name "/P4_3") (class "Default")
      (node (ref "IC6") (pin "37") (pinfunction "P1[23]/MCI1/__PWM1[4]/MISO0_37") (pintype "bidirectional"))
      (node (ref "R73") (pin "2") (pinfunction "2_2") (pintype "passive"))
    )
    (net (code "74") (name "/P4_4") (class "Default")
      (node (ref "IC6") (pin "38") (pinfunction "P1[24]/MCI2/__PWM1[5]/MOSI0_38") (pintype "bidirectional"))
      (node (ref "R74") (pin "2") (pinfunction "2_2") (pintype "passive"))
    )
    (net (code "75") (name "/P5_0") (class "Default")
      (node (ref "IC6") (pin "43") (pinfunction "P1[27]/CLKOUT__/~{USB_OVRCR}/__CAP0[1]_43") (pintype "bidirectional"))
      (node (ref "R75") (pin "2") (pinfunction "2_2") (pintype "passive"))
    )
    (net (code "76") (name "/P5_1") (class "Default")
      (node (ref "IC6") (pin "44") (pinfunction "P1[28]/MCOA2/__PCAP1[0]/__MAT0[0]_44") (pintype "bidirectional"))
      (node (ref "R77") (pin "2") (pinfunction "2_2") (pintype "passive"))
    )
    (net (code "77") (name "/P5_2") (class "Default")
      (node (ref "IC6") (pin "45") (pinfunction "P1[29]/MCOB2/__PCAP1[1]/__MAT0[1]_45") (pintype "bidirectional"))
      (node (ref "R79") (pin "2") (pinfunction "2_2") (pintype "passive"))
    )
    (net (code "78") (name "/P5_3") (class "Default")
      (node (ref "IC6") (pin "21") (pinfunction "P1[30]/VBUS/__AD0[4]_21") (pintype "bidirectional"))
      (node (ref "R81") (pin "2") (pinfunction "2_2") (pintype "passive"))
    )
    (net (code "79") (name "/P5_4") (class "Default")
      (node (ref "IC6") (pin "20") (pinfunction "P1[31]/SCK1/__AD0[5]_20") (pintype "bidirectional"))
      (node (ref "R85") (pin "2") (pinfunction "2_2") (pintype "passive"))
    )
    (net (code "80") (name "/PROG_RxD") (class "Default")
      (node (ref "IC6") (pin "99") (pinfunction "P0[3]/RXD0/AD0[6]_99") (pintype "bidirectional"))
      (node (ref "JP2") (pin "9") (pinfunction "9_9") (pintype "passive"))
    )
    (net (code "81") (name "/PROG_TxD") (class "Default")
      (node (ref "IC6") (pin "98") (pinfunction "P0[2]/TXD0/AD0[7]_98") (pintype "bidirectional"))
      (node (ref "JP2") (pin "7") (pinfunction "7_7") (pintype "passive"))
    )
    (net (code "82") (name "/RS0_A") (class "Default")
      (node (ref "R39") (pin "1") (pinfunction "1_1") (pintype "passive"))
    )
    (net (code "83") (name "/RS0_B") (class "Default")
      (node (ref "R47") (pin "1") (pinfunction "1_1") (pintype "passive"))
    )
    (net (code "84") (name "/RS0_C") (class "Default")
      (node (ref "R55") (pin "1") (pinfunction "1_1") (pintype "passive"))
    )
    (net (code "85") (name "/RS0_D") (class "Default")
      (node (ref "R65") (pin "1") (pinfunction "1_1") (pintype "passive"))
    )
    (net (code "86") (name "/RS1_A") (class "Default")
      (node (ref "R40") (pin "1") (pinfunction "1_1") (pintype "passive"))
    )
    (net (code "87") (name "/RS1_B") (class "Default")
      (node (ref "R48") (pin "1") (pinfunction "1_1") (pintype "passive"))
    )
    (net (code "88") (name "/RS1_C") (class "Default")
      (node (ref "R57") (pin "1") (pinfunction "1_1") (pintype "passive"))
    )
    (net (code "89") (name "/RS1_D") (class "Default")
      (node (ref "R66") (pin "1") (pinfunction "1_1") (pintype "passive"))
    )
    (net (code "90") (name "/RST") (class "Default")
      (node (ref "D1") (pin "1") (pinfunction "A_1") (pintype "passive"))
      (node (ref "IC6") (pin "17") (pinfunction "~{RESET}_17") (pintype "input"))
      (node (ref "JP2") (pin "10") (pinfunction "10_10") (pintype "passive"))
      (node (ref "R62") (pin "1") (pinfunction "1_1") (pintype "passive"))
      (node (ref "SW3") (pin "2") (pinfunction "2_2") (pintype "passive"))
    )
    (net (code "91") (name "/RSTO") (class "Default")
      (node (ref "IC6") (pin "14") (pinfunction "~{RSTOUT}_14") (pintype "output"))
    )
    (net (code "92") (name "/RST_A") (class "Default")
      (node (ref "R71") (pin "1") (pinfunction "1_1") (pintype "passive"))
    )
    (net (code "93") (name "/RST_B") (class "Default")
      (node (ref "R77") (pin "1") (pinfunction "1_1") (pintype "passive"))
    )
    (net (code "94") (name "/RXD0") (class "Default")
      (node (ref "IC6") (pin "91") (pinfunction "P1[9]/__ENET_RXD0_91") (pintype "bidirectional"))
    )
    (net (code "95") (name "/RXD1") (class "Default")
      (node (ref "IC6") (pin "90") (pinfunction "P1[10]/__ENET_RXD1_90") (pintype "bidirectional"))
    )
    (net (code "96") (name "/RXD_I") (class "Default")
      (node (ref "IC6") (pin "85") (pinfunction "P4[29]/TX_MCLK/__MAT2[1]/RXD3_85") (pintype "bidirectional"))
    )
    (net (code "97") (name "/RX_DV") (class "Default")
      (node (ref "IC6") (pin "92") (pinfunction "P1[8]/__ENET_CRS_92") (pintype "bidirectional"))
    )
    (net (code "98") (name "/RX_ER") (class "Default")
      (node (ref "IC6") (pin "89") (pinfunction "P1[14]/__ENET_RX_ER_89") (pintype "bidirectional"))
    )
    (net (code "99") (name "/SCL0") (class "Default")
      (node (ref "IC6") (pin "24") (pinfunction "P0[28]/SCL0/__USB_SCL_24") (pintype "bidirectional"))
      (node (ref "R83") (pin "1") (pinfunction "1_1") (pintype "passive"))
    )
    (net (code "100") (name "/SCL1") (class "Default")
      (node (ref "IC6") (pin "47") (pinfunction "P0[1]/TD1/RXD3/__SCL1_47") (pintype "bidirectional"))
      (node (ref "IC7") (pin "6") (pinfunction "SCL_6") (pintype "input"))
      (node (ref "R78") (pin "1") (pinfunction "1_1") (pintype "passive"))
    )
    (net (code "101") (name "/SCL2") (class "Default")
      (node (ref "IC6") (pin "49") (pinfunction "P0[11]/RXD2/__SCL2/MAT3[1]_49") (pintype "bidirectional"))
      (node (ref "R82") (pin "1") (pinfunction "1_1") (pintype "passive"))
    )
    (net (code "102") (name "/SDA0") (class "Default")
      (node (ref "IC6") (pin "25") (pinfunction "P0[27]/SDA0/__USB_SDA_25") (pintype "bidirectional"))
      (node (ref "R84") (pin "1") (pinfunction "1_1") (pintype "passive"))
    )
    (net (code "103") (name "/SDA1") (class "Default")
      (node (ref "IC6") (pin "46") (pinfunction "P0[0]/RD1/TXD3/__SDA1_46") (pintype "bidirectional"))
      (node (ref "IC7") (pin "5") (pinfunction "SDA_5") (pintype "bidirectional"))
      (node (ref "R76") (pin "1") (pinfunction "1_1") (pintype "passive"))
    )
    (net (code "104") (name "/SDA2") (class "Default")
      (node (ref "IC6") (pin "48") (pinfunction "P0[10]/TXD2/__SDA2/MAT3[0]_48") (pintype "bidirectional"))
      (node (ref "R80") (pin "1") (pinfunction "1_1") (pintype "passive"))
    )
    (net (code "105") (name "/SWCLK") (class "Default")
      (node (ref "IC6") (pin "5") (pinfunction "TCK/SWDCLK_5") (pintype "input"))
      (node (ref "JP2") (pin "4") (pinfunction "4_4") (pintype "passive"))
      (node (ref "R58") (pin "2") (pinfunction "2_2") (pintype "passive"))
    )
    (net (code "106") (name "/SWDIO") (class "Default")
      (node (ref "IC6") (pin "3") (pinfunction "TMS/SWDIO_3") (pintype "bidirectional"))
      (node (ref "JP2") (pin "2") (pinfunction "2_2") (pintype "passive"))
      (node (ref "R54") (pin "1") (pinfunction "1_1") (pintype "passive"))
    )
    (net (code "107") (name "/THERMn") (class "Default")
      (node (ref "IC6") (pin "32") (pinfunction "P1[18]/USB_UP_LED/PWM1[1]/_CAP1[0]_32") (pintype "bidirectional"))
    )
    (net (code "108") (name "/TRST") (class "Default")
      (node (ref "IC6") (pin "4") (pinfunction "~{TRST}_4") (pintype "input"))
      (node (ref "R56") (pin "1") (pinfunction "1_1") (pintype "passive"))
    )
    (net (code "109") (name "/TXD0") (class "Default")
      (node (ref "IC6") (pin "95") (pinfunction "P1[0]/__ENET_TXD0_95") (pintype "bidirectional"))
    )
    (net (code "110") (name "/TXD1") (class "Default")
      (node (ref "IC6") (pin "94") (pinfunction "P1[1]/__ENET_TXD1_94") (pintype "bidirectional"))
    )
    (net (code "111") (name "/TXDISABLE_A") (class "Default")
      (node (ref "R37") (pin "1") (pinfunction "1_1") (pintype "passive"))
    )
    (net (code "112") (name "/TXDISABLE_B") (class "Default")
      (node (ref "R45") (pin "1") (pinfunction "1_1") (pintype "passive"))
    )
    (net (code "113") (name "/TXDISABLE_C") (class "Default")
      (node (ref "R52") (pin "1") (pinfunction "1_1") (pintype "passive"))
    )
    (net (code "114") (name "/TXDISABLE_D") (class "Default")
      (node (ref "R63") (pin "1") (pinfunction "1_1") (pintype "passive"))
    )
    (net (code "115") (name "/TXD_O") (class "Default")
      (node (ref "IC6") (pin "82") (pinfunction "P4[28]/RX_MCLK/__MAT2[0]/TXD3_82") (pintype "bidirectional"))
    )
    (net (code "116") (name "/TXFAULT_A") (class "Default")
      (node (ref "R41") (pin "1") (pinfunction "1_1") (pintype "passive"))
    )
    (net (code "117") (name "/TXFAULT_B") (class "Default")
      (node (ref "R49") (pin "1") (pinfunction "1_1") (pintype "passive"))
    )
    (net (code "118") (name "/TXFAULT_C") (class "Default")
      (node (ref "R59") (pin "1") (pinfunction "1_1") (pintype "passive"))
    )
    (net (code "119") (name "/TXFAULT_D") (class "Default")
      (node (ref "R67") (pin "1") (pinfunction "1_1") (pintype "passive"))
    )
    (net (code "120") (name "/TX_CLK") (class "Default")
      (node (ref "IC6") (pin "88") (pinfunction "P1[15]/__ENET_REF_CLK_88") (pintype "bidirectional"))
    )
    (net (code "121") (name "/TX_EN") (class "Default")
      (node (ref "IC6") (pin "93") (pinfunction "P1[4]/__ENET_TX_EN_93") (pintype "bidirectional"))
    )
    (net (code "128") (name "GND") (class "Default")
      (node (ref "C17") (pin "1") (pinfunction "1_1") (pintype "passive"))
      (node (ref "C18") (pin "1") (pinfunction "1_1") (pintype "passive"))
      (node (ref "C19") (pin "1") (pinfunction "1_1") (pintype "passive"))
      (node (ref "C20") (pin "1") (pinfunction "1_1") (pintype "passive"))
      (node (ref "C21") (pin "1") (pinfunction "1_1") (pintype "passive"))
      (node (ref "C22") (pin "1") (pinfunction "1_1") (pintype "passive"))
      (node (ref "C23") (pin "1") (pinfunction "1_1") (pintype "passive"))
      (node (ref "C24") (pin "1") (pinfunction "1_1") (pintype "passive"))
      (node (ref "C25") (pin "2") (pinfunction "2_2") (pintype "passive"))
      (node (ref "C26") (pin "1") (pinfunction "1_1") (pintype "passive"))
      (node (ref "C27") (pin "1") (pinfunction "1_1") (pintype "passive"))
      (node (ref "C28") (pin "1") (pinfunction "1_1") (pintype "passive"))
      (node (ref "C29") (pin "1") (pinfunction "1_1") (pintype "passive"))
      (node (ref "C30") (pin "1") (pinfunction "1_1") (pintype "passive"))
      (node (ref "C31") (pin "1") (pinfunction "1_1") (pintype "passive"))
      (node (ref "C32") (pin "1") (pinfunction "1_1") (pintype "passive"))
      (node (ref "IC6") (pin "11") (pinfunction "VSSA_11") (pintype "power_in"))
      (node (ref "IC6") (pin "15") (pinfunction "VREFN_15") (pintype "power_in"))
      (node (ref "IC6") (pin "31") (pinfunction "VSS_31") (pintype "power_in"))
      (node (ref "IC6") (pin "41") (pinfunction "VSS_41") (pintype "power_in"))
      (node (ref "IC6") (pin "55") (pinfunction "VSS_55") (pintype "power_in"))
      (node (ref "IC6") (pin "72") (pinfunction "VSS_72") (pintype "power_in"))
      (node (ref "IC6") (pin "83") (pinfunction "VSS_83") (pintype "power_in"))
      (node (ref "IC6") (pin "97") (pinfunction "VSS_97") (pintype "power_in"))
      (node (ref "IC7") (pin "1") (pinfunction "A0_1") (pintype "input"))
      (node (ref "IC7") (pin "2") (pinfunction "A1_2") (pintype "input"))
      (node (ref "IC7") (pin "3") (pinfunction "A2_3") (pintype "input"))
      (node (ref "IC7") (pin "4") (pinfunction "GND_4") (pintype "power_in"))
      (node (ref "IC7") (pin "7") (pinfunction "WP_7") (pintype "passive"))
      (node (ref "IC8") (pin "1") (pinfunction "Vss_1") (pintype "power_in"))
      (node (ref "JP2") (pin "3") (pinfunction "3_3") (pintype "passive"))
      (node (ref "JP2") (pin "5") (pinfunction "5_5") (pintype "passive"))
      (node (ref "R58") (pin "1") (pinfunction "1_1") (pintype "passive"))
      (node (ref "SW3") (pin "1") (pinfunction "1_1") (pintype "passive"))
    )
    (net (code "129") (name "Net-(D1-C)") (class "Default")
      (node (ref "D1") (pin "3") (pinfunction "C_3") (pintype "passive"))
      (node (ref "IC8") (pin "2") (pinfunction "~{RST}_2") (pintype "output"))
    )
    (net (code "130") (name "Net-(IC6A-RTCX1)") (class "Default")
      (node (ref "IC6") (pin "16") (pinfunction "RTCX1_16") (pintype "input"))
      (node (ref "TP1") (pin "1") (pintype "passive"))
    )
    (net (code "131") (name "Net-(IC6A-RTCX2)") (class "Default")
      (node (ref "IC6") (pin "18") (pinfunction "RTCX2_18") (pintype "output"))
      (node (ref "TP2") (pin "1") (pintype "passive"))
    )
    (net (code "132") (name "Net-(IC6A-XTAL1)") (class "Default")
      (node (ref "C17") (pin "2") (pinfunction "2_2") (pintype "passive"))
      (node (ref "IC6") (pin "22") (pinfunction "XTAL1_22") (pintype "input"))
      (node (ref "X1") (pin "1") (pinfunction "1_1") (pintype "passive"))
    )
    (net (code "133") (name "Net-(IC6A-XTAL2)") (class "Default")
      (node (ref "C19") (pin "2") (pinfunction "2_2") (pintype "passive"))
      (node (ref "IC6") (pin "23") (pinfunction "XTAL2_23") (pintype "output"))
      (node (ref "X1") (pin "2") (pinfunction "2_2") (pintype "passive"))
    )
    (net (code "134") (name "P3V3") (class "Default")
      (node (ref "C18") (pin "2") (pinfunction "2_2") (pintype "passive"))
      (node (ref "C20") (pin "2") (pinfunction "2_2") (pintype "passive"))
      (node (ref "C22") (pin "2") (pinfunction "2_2") (pintype "passive"))
      (node (ref "C23") (pin "2") (pinfunction "2_2") (pintype "passive"))
      (node (ref "C24") (pin "2") (pinfunction "2_2") (pintype "passive"))
      (node (ref "C25") (pin "1") (pinfunction "1_1") (pintype "passive"))
      (node (ref "C26") (pin "2") (pinfunction "2_2") (pintype "passive"))
      (node (ref "C27") (pin "2") (pinfunction "2_2") (pintype "passive"))
      (node (ref "C28") (pin "2") (pinfunction "2_2") (pintype "passive"))
      (node (ref "C29") (pin "2") (pinfunction "2_2") (pintype "passive"))
      (node (ref "C30") (pin "2") (pinfunction "2_2") (pintype "passive"))
      (node (ref "C31") (pin "2") (pinfunction "2_2") (pintype "passive"))
      (node (ref "C32") (pin "2") (pinfunction "2_2") (pintype "passive"))
      (node (ref "FB1") (pin "2") (pinfunction "2_2") (pintype "passive"))
      (node (ref "IC6") (pin "19") (pinfunction "VBAT_19") (pintype "power_in"))
      (node (ref "IC6") (pin "28") (pinfunction "VDD(3V3)_28") (pintype "power_in"))
      (node (ref "IC6") (pin "42") (pinfunction "VDD(REG)(3V3)_42") (pintype "power_in"))
      (node (ref "IC6") (pin "54") (pinfunction "VDD(3V3)_54") (pintype "power_in"))
      (node (ref "IC6") (pin "71") (pinfunction "VDD(3V3)_71") (pintype "power_in"))
      (node (ref "IC6") (pin "84") (pinfunction "VDD(REG)(3V3)_84") (pintype "power_in"))
      (node (ref "IC6") (pin "96") (pinfunction "VDD(3V3)_96") (pintype "power_in"))
      (node (ref "IC7") (pin "8") (pinfunction "VCC_8") (pintype "power_in"))
      (node (ref "IC8") (pin "3") (pinfunction "Vcc_3") (pintype "power_in"))
      (node (ref "JP2") (pin "1") (pinfunction "1_1") (pintype "passive"))
      (node (ref "R27") (pin "1") (pinfunction "1_1") (pintype "passive"))
      (node (ref "R54") (pin "2") (pinfunction "2_2") (pintype "passive"))
      (node (ref "R56") (pin "2") (pinfunction "2_2") (pintype "passive"))
      (node (ref "R62") (pin "2") (pinfunction "2_2") (pintype "passive"))
      (node (ref "R76") (pin "2") (pinfunction "2_2") (pintype "passive"))
      (node (ref "R78") (pin "2") (pinfunction "2_2") (pintype "passive"))
      (node (ref "R80") (pin "2") (pinfunction "2_2") (pintype "passive"))
      (node (ref "R82") (pin "2") (pinfunction "2_2") (pintype "passive"))
      (node (ref "R83") (pin "2") (pinfunction "2_2") (pintype "passive"))
      (node (ref "R84") (pin "2") (pinfunction "2_2") (pintype "passive"))
    )
    (net (code "135") (name "unconnected-(IC6A-N.C.-Pad13)") (class "Default")
      (node (ref "IC6") (pin "13") (pinfunction "N.C._13") (pintype "tri_state"))
    )
    (net (code "136") (name "unconnected-(IC6A-P2[7]{slash}RD2{slash}__RTS1-Pad66)") (class "Default")
      (node (ref "IC6") (pin "66") (pinfunction "P2[7]/RD2/__RTS1_66") (pintype "bidirectional"))
    )
    (net (code "137") (name "unconnected-(IC6A-RTCK-Pad100)") (class "Default")
      (node (ref "IC6") (pin "100") (pinfunction "RTCK_100") (pintype "output"))
    )
    (net (code "138") (name "unconnected-(IC6C-P0[24]{slash}AD0[1]{slash}__I2SRX_WS{slash}__CAP3[1]-Pad8)") (class "Default")
      (node (ref "IC6") (pin "8") (pinfunction "P0[24]/AD0[1]/__I2SRX_WS/__CAP3[1]_8") (pintype "bidirectional"))
    )
    (net (code "139") (name "unconnected-(IC6C-P0[30]{slash}USB_D--Pad30)") (class "Default")
      (node (ref "IC6") (pin "30") (pinfunction "P0[30]/USB_D-_30") (pintype "bidirectional"))
    )
  )
)
